# design.net
KiCad netlist of a schematic drawn in Altium Designer
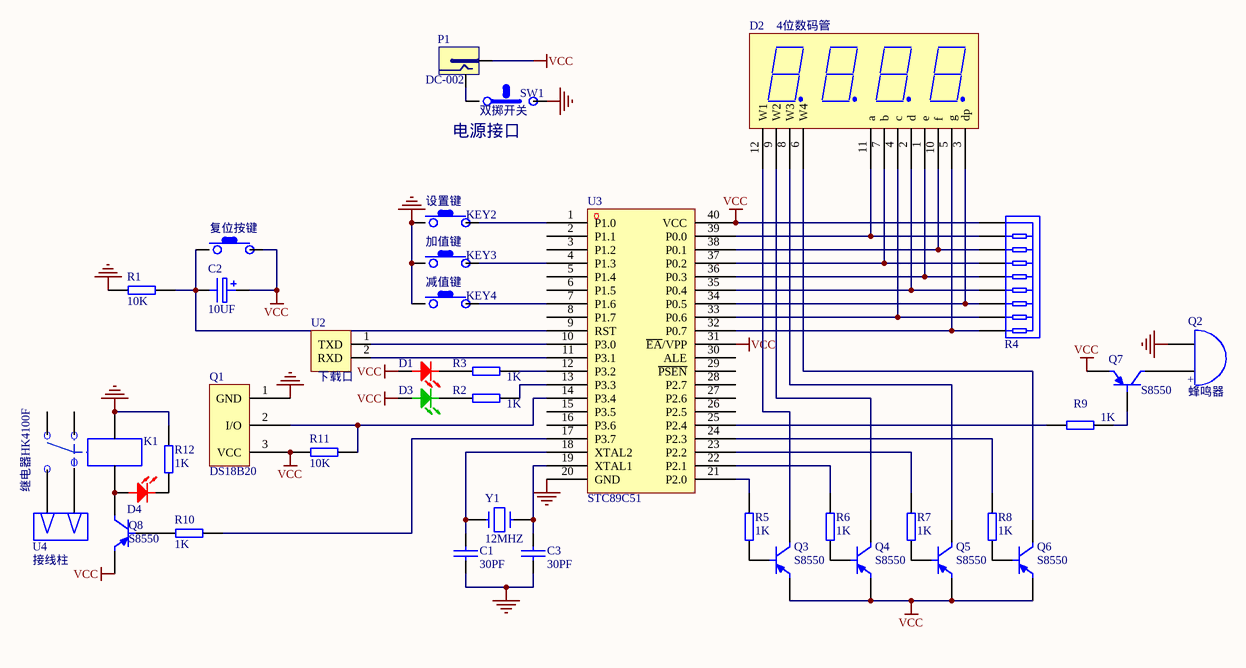
[diagram p0: 水温控制系统原理图.SchDoc]

(export (version "E")
  (design (tool "Eeschema 10.0.6"))
  (components
    (comp (ref "C1") (value "30PF") (footprint "R38") (libsource (lib "元件库") (part "瓷片电容")))
    (comp (ref "C2") (value "10UF") (footprint "CD4") (libsource (lib "元件库") (part "电解电容")))
    (comp (ref "C3") (value "30PF") (footprint "R38") (libsource (lib "元件库") (part "瓷片电容")))
    (comp (ref "D1") (value "LED-RED") (footprint "LED-RED") (libsource (lib "元件库") (part "LED-RED")))
    (comp (ref "D2") (value "4位数码管") (footprint "3641B") (libsource (lib "元件库") (part "4位数码管")))
    (comp (ref "D3") (value "LED-GREEN") (footprint "LED-GREEN") (libsource (lib "元件库") (part "LED-GREEN")))
    (comp (ref "D4") (value "LED-RED") (footprint "LED-RED") (libsource (lib "元件库") (part "LED-RED")))
    (comp (ref "K1") (value "继电器HK4100F") (footprint "HK4100F") (libsource (lib "元件库") (part "继电器HK4100F")))
    (comp (ref "KEY1") (value "复位按键") (footprint "SW") (libsource (lib "元件库") (part "微动开关")))
    (comp (ref "KEY2") (value "设置键") (footprint "SW") (libsource (lib "元件库") (part "微动开关")))
    (comp (ref "KEY3") (value "加值键") (footprint "SW") (libsource (lib "元件库") (part "微动开关")))
    (comp (ref "KEY4") (value "减值键") (footprint "SW") (libsource (lib "元件库") (part "微动开关")))
    (comp (ref "P1") (value "DC-002") (footprint "DC-002") (libsource (lib "元件库") (part "DC-002")))
    (comp (ref "Q1") (value "DS18B20") (footprint "XH3P") (libsource (lib "元件库") (part "DS18B20")))
    (comp (ref "Q2") (value "蜂鸣器") (footprint "蜂鸣器") (libsource (lib "元件库") (part "蜂鸣器")))
    (comp (ref "Q3") (value "S8550") (footprint "三极管") (libsource (lib "元件库") (part "S8550")))
    (comp (ref "Q4") (value "S8550") (footprint "三极管") (libsource (lib "元件库") (part "S8550")))
    (comp (ref "Q5") (value "S8550") (footprint "三极管") (libsource (lib "元件库") (part "S8550")))
    (comp (ref "Q6") (value "S8550") (footprint "三极管") (libsource (lib "元件库") (part "S8550")))
    (comp (ref "Q7") (value "S8550") (footprint "三极管") (libsource (lib "元件库") (part "S8550")))
    (comp (ref "Q8") (value "S8550") (footprint "三极管") (libsource (lib "元件库") (part "S8550")))
    (comp (ref "R1") (value "10K") (footprint "AXIAL-0.3") (libsource (lib "元件库") (part "RES")))
    (comp (ref "R2") (value "1K") (footprint "AXIAL-0.3") (libsource (lib "元件库") (part "RES")))
    (comp (ref "R3") (value "1K") (footprint "AXIAL-0.3") (libsource (lib "元件库") (part "RES")))
    (comp (ref "R4") (value "10k") (footprint "R*9") (libsource (lib "元件库") (part "排阻")))
    (comp (ref "R5") (value "1K") (footprint "AXIAL-0.3") (libsource (lib "元件库") (part "RES")))
    (comp (ref "R6") (value "1K") (footprint "AXIAL-0.3") (libsource (lib "元件库") (part "RES")))
    (comp (ref "R7") (value "1K") (footprint "AXIAL-0.3") (libsource (lib "元件库") (part "RES")))
    (comp (ref "R8") (value "1K") (footprint "AXIAL-0.3") (libsource (lib "元件库") (part "RES")))
    (comp (ref "R9") (value "1K") (footprint "AXIAL-0.3") (libsource (lib "元件库") (part "RES")))
    (comp (ref "R10") (value "1K") (footprint "AXIAL-0.3") (libsource (lib "元件库") (part "RES")))
    (comp (ref "R11") (value "10K") (footprint "AXIAL-0.3") (libsource (lib "元件库") (part "RES")))
    (comp (ref "R12") (value "1K") (footprint "AXIAL-0.3") (libsource (lib "元件库") (part "RES")))
    (comp (ref "SW1") (value "双掷开关") (footprint "SS12D07G5") (libsource (lib "元件库") (part "双掷开关")))
    (comp (ref "U2") (value "下载口") (footprint "HDR2") (libsource (lib "元件库") (part "下载口")))
    (comp (ref "U3") (value "STC89C51") (footprint "DIP40") (libsource (lib "元件库") (part "STC89C52")))
    (comp (ref "U4") (value "接线柱") (footprint "KF301-2P") (libsource (lib "元件库") (part "接线柱")))
    (comp (ref "Y1") (value "12MHZ") (footprint "XTAL") (libsource (lib "元件库") (part "XTAL")))
  )
  (nets
    (net (code "1") (name "GND") (class "Default")
      (node (ref "C1") (pin "2") (pinfunction "2_2") (pintype "passive"))
      (node (ref "C3") (pin "1") (pinfunction "1_1") (pintype "passive"))
      (node (ref "K1") (pin "5") (pinfunction "5_5") (pintype "passive"))
      (node (ref "KEY2") (pin "1") (pinfunction "3_1") (pintype "passive"))
      (node (ref "KEY3") (pin "1") (pinfunction "3_1") (pintype "passive"))
      (node (ref "KEY4") (pin "1") (pinfunction "3_1") (pintype "passive"))
      (node (ref "Q1") (pin "1") (pinfunction "GND_1") (pintype "passive"))
      (node (ref "Q2") (pin "2") (pinfunction "2_2") (pintype "passive"))
      (node (ref "R1") (pin "1") (pinfunction "1_1") (pintype "passive"))
      (node (ref "R12") (pin "1") (pinfunction "1_1") (pintype "passive"))
      (node (ref "SW1") (pin "2") (pinfunction "2_2") (pintype "passive"))
      (node (ref "U3") (pin "20") (pinfunction "GND_20") (pintype "passive"))
    )
    (net (code "2") (name "Net-(C2-E)") (class "Default")
      (node (ref "C2") (pin "2") (pinfunction "E_2") (pintype "passive"))
      (node (ref "KEY1") (pin "1") (pinfunction "3_1") (pintype "passive"))
      (node (ref "R1") (pin "2") (pinfunction "2_2") (pintype "passive"))
      (node (ref "U3") (pin "9") (pinfunction "RST_9") (pintype "passive"))
    )
    (net (code "3") (name "Net-(D1-Pad2)") (class "Default")
      (node (ref "D1") (pin "2") (pintype "passive"))
      (node (ref "R3") (pin "2") (pinfunction "2_2") (pintype "passive"))
    )
    (net (code "4") (name "Net-(D2-W1)") (class "Default")
      (node (ref "D2") (pin "12") (pinfunction "W1_12") (pintype "passive"))
      (node (ref "Q3") (pin "3") (pinfunction "C_3") (pintype "passive"))
    )
    (net (code "5") (name "Net-(D2-W2)") (class "Default")
      (node (ref "D2") (pin "9") (pinfunction "W2_9") (pintype "passive"))
      (node (ref "Q4") (pin "3") (pinfunction "C_3") (pintype "passive"))
    )
    (net (code "6") (name "Net-(D2-W3)") (class "Default")
      (node (ref "D2") (pin "8") (pinfunction "W3_8") (pintype "passive"))
      (node (ref "Q5") (pin "3") (pinfunction "C_3") (pintype "passive"))
    )
    (net (code "7") (name "Net-(D2-W4)") (class "Default")
      (node (ref "D2") (pin "6") (pinfunction "W4_6") (pintype "passive"))
      (node (ref "Q6") (pin "3") (pinfunction "C_3") (pintype "passive"))
    )
    (net (code "8") (name "Net-(D2-a)") (class "Default")
      (node (ref "D2") (pin "11") (pinfunction "a_11") (pintype "passive"))
      (node (ref "R4") (pin "2") (pinfunction "2_2") (pintype "passive"))
      (node (ref "U3") (pin "39") (pinfunction "P0.0_39") (pintype "passive"))
    )
    (net (code "9") (name "Net-(D2-b)") (class "Default")
      (node (ref "D2") (pin "7") (pinfunction "b_7") (pintype "passive"))
      (node (ref "R4") (pin "4") (pinfunction "4_4") (pintype "passive"))
      (node (ref "U3") (pin "37") (pinfunction "P0.2_37") (pintype "passive"))
    )
    (net (code "10") (name "Net-(D2-c)") (class "Default")
      (node (ref "D2") (pin "4") (pinfunction "c_4") (pintype "passive"))
      (node (ref "R4") (pin "8") (pinfunction "8_8") (pintype "passive"))
      (node (ref "U3") (pin "33") (pinfunction "P0.6_33") (pintype "passive"))
    )
    (net (code "11") (name "Net-(D2-d)") (class "Default")
      (node (ref "D2") (pin "2") (pinfunction "d_2") (pintype "passive"))
      (node (ref "R4") (pin "6") (pinfunction "6_6") (pintype "passive"))
      (node (ref "U3") (pin "35") (pinfunction "P0.4_35") (pintype "passive"))
    )
    (net (code "12") (name "Net-(D2-dp)") (class "Default")
      (node (ref "D2") (pin "3") (pinfunction "dp_3") (pintype "passive"))
      (node (ref "R4") (pin "7") (pinfunction "7_7") (pintype "passive"))
      (node (ref "U3") (pin "34") (pinfunction "P0.5_34") (pintype "passive"))
    )
    (net (code "13") (name "Net-(D2-e)") (class "Default")
      (node (ref "D2") (pin "1") (pinfunction "e_1") (pintype "passive"))
      (node (ref "R4") (pin "5") (pinfunction "5_5") (pintype "passive"))
      (node (ref "U3") (pin "36") (pinfunction "P0.3_36") (pintype "passive"))
    )
    (net (code "14") (name "Net-(D2-f)") (class "Default")
      (node (ref "D2") (pin "10") (pinfunction "f_10") (pintype "passive"))
      (node (ref "R4") (pin "3") (pinfunction "3_3") (pintype "passive"))
      (node (ref "U3") (pin "38") (pinfunction "P0.1_38") (pintype "passive"))
    )
    (net (code "15") (name "Net-(D2-g)") (class "Default")
      (node (ref "D2") (pin "5") (pinfunction "g_5") (pintype "passive"))
      (node (ref "R4") (pin "9") (pinfunction "9_9") (pintype "passive"))
      (node (ref "U3") (pin "32") (pinfunction "P0.7_32") (pintype "passive"))
    )
    (net (code "16") (name "Net-(D3-Pad2)") (class "Default")
      (node (ref "D3") (pin "2") (pintype "passive"))
      (node (ref "R2") (pin "2") (pinfunction "2_2") (pintype "passive"))
    )
    (net (code "17") (name "Net-(D4-Pad2)") (class "Default")
      (node (ref "D4") (pin "2") (pintype "passive"))
      (node (ref "R12") (pin "2") (pinfunction "2_2") (pintype "passive"))
    )
    (net (code "18") (name "Net-(K1-Pad1)") (class "Default")
      (node (ref "K1") (pin "1") (pinfunction "1_1") (pintype "passive"))
      (node (ref "U4") (pin "1") (pinfunction "1_1") (pintype "passive"))
    )
    (net (code "19") (name "Net-(K1-Pad4)") (class "Default")
      (node (ref "K1") (pin "4") (pinfunction "4_4") (pintype "passive"))
      (node (ref "U4") (pin "2") (pinfunction "2_2") (pintype "passive"))
    )
    (net (code "20") (name "Net-(KEY2-4)") (class "Default")
      (node (ref "KEY2") (pin "2") (pinfunction "4_2") (pintype "passive"))
      (node (ref "U3") (pin "1") (pinfunction "P1.0_1") (pintype "passive"))
    )
    (net (code "21") (name "Net-(KEY3-4)") (class "Default")
      (node (ref "KEY3") (pin "2") (pinfunction "4_2") (pintype "passive"))
      (node (ref "U3") (pin "4") (pinfunction "P1.3_4") (pintype "passive"))
    )
    (net (code "22") (name "Net-(KEY4-4)") (class "Default")
      (node (ref "KEY4") (pin "2") (pinfunction "4_2") (pintype "passive"))
      (node (ref "U3") (pin "7") (pinfunction "P1.6_7") (pintype "passive"))
    )
    (net (code "23") (name "Net-(P1-Pad2)") (class "Default")
      (node (ref "P1") (pin "2") (pinfunction "2_2") (pintype "passive"))
      (node (ref "SW1") (pin "1") (pinfunction "1_1") (pintype "passive"))
    )
    (net (code "24") (name "Net-(Q1-I{slash}O)") (class "Default")
      (node (ref "Q1") (pin "2") (pinfunction "I/O_2") (pintype "passive"))
      (node (ref "R11") (pin "1") (pinfunction "1_1") (pintype "passive"))
      (node (ref "U3") (pin "14") (pinfunction "P3.4_14") (pintype "passive"))
    )
    (net (code "25") (name "Net-(Q3-B)") (class "Default")
      (node (ref "Q3") (pin "2") (pinfunction "B_2") (pintype "passive"))
      (node (ref "R5") (pin "2") (pinfunction "2_2") (pintype "passive"))
    )
    (net (code "26") (name "Net-(Q4-B)") (class "Default")
      (node (ref "Q4") (pin "2") (pinfunction "B_2") (pintype "passive"))
      (node (ref "R6") (pin "2") (pinfunction "2_2") (pintype "passive"))
    )
    (net (code "27") (name "Net-(Q5-B)") (class "Default")
      (node (ref "Q5") (pin "2") (pinfunction "B_2") (pintype "passive"))
      (node (ref "R7") (pin "2") (pinfunction "2_2") (pintype "passive"))
    )
    (net (code "28") (name "Net-(Q6-B)") (class "Default")
      (node (ref "Q6") (pin "2") (pinfunction "B_2") (pintype "passive"))
      (node (ref "R8") (pin "2") (pinfunction "2_2") (pintype "passive"))
    )
    (net (code "29") (name "Net-(Q7-B)") (class "Default")
      (node (ref "Q7") (pin "2") (pinfunction "B_2") (pintype "passive"))
      (node (ref "R9") (pin "2") (pinfunction "2_2") (pintype "passive"))
    )
    (net (code "30") (name "Net-(Q7-C)") (class "Default")
      (node (ref "Q2") (pin "1") (pinfunction "1_1") (pintype "passive"))
      (node (ref "Q7") (pin "3") (pinfunction "C_3") (pintype "passive"))
    )
    (net (code "31") (name "Net-(Q8-B)") (class "Default")
      (node (ref "Q8") (pin "2") (pinfunction "B_2") (pintype "passive"))
      (node (ref "R10") (pin "1") (pinfunction "1_1") (pintype "passive"))
    )
    (net (code "32") (name "Net-(Q8-C)") (class "Default")
      (node (ref "D4") (pin "1") (pintype "passive"))
      (node (ref "K1") (pin "2") (pinfunction "2_2") (pintype "passive"))
      (node (ref "Q8") (pin "3") (pinfunction "C_3") (pintype "passive"))
    )
    (net (code "33") (name "Net-(U2-RXD)") (class "Default")
      (node (ref "U2") (pin "2") (pinfunction "RXD_2") (pintype "passive"))
      (node (ref "U3") (pin "11") (pinfunction "P3.1_11") (pintype "passive"))
    )
    (net (code "34") (name "Net-(U2-TXD)") (class "Default")
      (node (ref "U2") (pin "1") (pinfunction "TXD_1") (pintype "passive"))
      (node (ref "U3") (pin "10") (pinfunction "P3.0_10") (pintype "passive"))
    )
    (net (code "35") (name "Net-(U3-P2.0)") (class "Default")
      (node (ref "R5") (pin "1") (pinfunction "1_1") (pintype "passive"))
      (node (ref "U3") (pin "21") (pinfunction "P2.0_21") (pintype "passive"))
    )
    (net (code "36") (name "Net-(U3-P2.1)") (class "Default")
      (node (ref "R6") (pin "1") (pinfunction "1_1") (pintype "passive"))
      (node (ref "U3") (pin "22") (pinfunction "P2.1_22") (pintype "passive"))
    )
    (net (code "37") (name "Net-(U3-P2.2)") (class "Default")
      (node (ref "R7") (pin "1") (pinfunction "1_1") (pintype "passive"))
      (node (ref "U3") (pin "23") (pinfunction "P2.2_23") (pintype "passive"))
    )
    (net (code "38") (name "Net-(U3-P2.3)") (class "Default")
      (node (ref "R8") (pin "1") (pinfunction "1_1") (pintype "passive"))
      (node (ref "U3") (pin "24") (pinfunction "P2.3_24") (pintype "passive"))
    )
    (net (code "39") (name "Net-(U3-P2.4)") (class "Default")
      (node (ref "R9") (pin "1") (pinfunction "1_1") (pintype "passive"))
      (node (ref "U3") (pin "25") (pinfunction "P2.4_25") (pintype "passive"))
    )
    (net (code "40") (name "Net-(U3-P3.2)") (class "Default")
      (node (ref "R3") (pin "1") (pinfunction "1_1") (pintype "passive"))
      (node (ref "U3") (pin "12") (pinfunction "P3.2_12") (pintype "passive"))
    )
    (net (code "41") (name "Net-(U3-P3.3)") (class "Default")
      (node (ref "R2") (pin "1") (pinfunction "1_1") (pintype "passive"))
      (node (ref "U3") (pin "13") (pinfunction "P3.3_13") (pintype "passive"))
    )
    (net (code "42") (name "Net-(U3-P3.7)") (class "Default")
      (node (ref "R10") (pin "2") (pinfunction "2_2") (pintype "passive"))
      (node (ref "U3") (pin "17") (pinfunction "P3.7_17") (pintype "passive"))
    )
    (net (code "43") (name "Net-(U3-XTAL1)") (class "Default")
      (node (ref "C3") (pin "2") (pinfunction "2_2") (pintype "passive"))
      (node (ref "U3") (pin "19") (pinfunction "XTAL1_19") (pintype "passive"))
      (node (ref "Y1") (pin "1") (pinfunction "1_1") (pintype "passive"))
    )
    (net (code "44") (name "Net-(U3-XTAL2)") (class "Default")
      (node (ref "C1") (pin "1") (pinfunction "1_1") (pintype "passive"))
      (node (ref "U3") (pin "18") (pinfunction "XTAL2_18") (pintype "passive"))
      (node (ref "Y1") (pin "2") (pinfunction "2_2") (pintype "passive"))
    )
    (net (code "45") (name "VCC") (class "Default")
      (node (ref "C2") (pin "1") (pinfunction "1_1") (pintype "passive"))
      (node (ref "D1") (pin "1") (pintype "passive"))
      (node (ref "D3") (pin "1") (pintype "passive"))
      (node (ref "KEY1") (pin "2") (pinfunction "4_2") (pintype "passive"))
      (node (ref "P1") (pin "1") (pinfunction "1_1") (pintype "passive"))
      (node (ref "Q1") (pin "3") (pinfunction "VCC_3") (pintype "passive"))
      (node (ref "Q3") (pin "1") (pinfunction "E_1") (pintype "passive"))
      (node (ref "Q4") (pin "1") (pinfunction "E_1") (pintype "passive"))
      (node (ref "Q5") (pin "1") (pinfunction "E_1") (pintype "passive"))
      (node (ref "Q6") (pin "1") (pinfunction "E_1") (pintype "passive"))
      (node (ref "Q7") (pin "1") (pinfunction "E_1") (pintype "passive"))
      (node (ref "Q8") (pin "1") (pinfunction "E_1") (pintype "passive"))
      (node (ref "R11") (pin "2") (pinfunction "2_2") (pintype "passive"))
      (node (ref "R4") (pin "1") (pinfunction "1_1") (pintype "passive"))
      (node (ref "U3") (pin "31") (pinfunction "~{EA}/VPP_31") (pintype "passive"))
      (node (ref "U3") (pin "40") (pinfunction "VCC_40") (pintype "passive"))
    )
    (net (code "46") (name "unconnected-(K1-Pad3)") (class "Default")
      (node (ref "K1") (pin "3") (pinfunction "3_3") (pintype "passive"))
    )
    (net (code "47") (name "unconnected-(K1-Pad6)") (class "Default")
      (node (ref "K1") (pin "6") (pinfunction "6_6") (pintype "passive"))
    )
    (net (code "48") (name "unconnected-(U3-ALE-Pad30)") (class "Default")
      (node (ref "U3") (pin "30") (pinfunction "ALE_30") (pintype "passive"))
    )
    (net (code "49") (name "unconnected-(U3-P1.1-Pad2)") (class "Default")
      (node (ref "U3") (pin "2") (pinfunction "P1.1_2") (pintype "passive"))
    )
    (net (code "50") (name "unconnected-(U3-P1.2-Pad3)") (class "Default")
      (node (ref "U3") (pin "3") (pinfunction "P1.2_3") (pintype "passive"))
    )
    (net (code "51") (name "unconnected-(U3-P1.4-Pad5)") (class "Default")
      (node (ref "U3") (pin "5") (pinfunction "P1.4_5") (pintype "passive"))
    )
    (net (code "52") (name "unconnected-(U3-P1.5-Pad6)") (class "Default")
      (node (ref "U3") (pin "6") (pinfunction "P1.5_6") (pintype "passive"))
    )
    (net (code "53") (name "unconnected-(U3-P1.7-Pad8)") (class "Default")
      (node (ref "U3") (pin "8") (pinfunction "P1.7_8") (pintype "passive"))
    )
    (net (code "54") (name "unconnected-(U3-P2.5-Pad26)") (class "Default")
      (node (ref "U3") (pin "26") (pinfunction "P2.5_26") (pintype "passive"))
    )
    (net (code "55") (name "unconnected-(U3-P2.6-Pad27)") (class "Default")
      (node (ref "U3") (pin "27") (pinfunction "P2.6_27") (pintype "passive"))
    )
    (net (code "56") (name "unconnected-(U3-P2.7-Pad28)") (class "Default")
      (node (ref "U3") (pin "28") (pinfunction "P2.7_28") (pintype "passive"))
    )
    (net (code "57") (name "unconnected-(U3-P3.5-Pad15)") (class "Default")
      (node (ref "U3") (pin "15") (pinfunction "P3.5_15") (pintype "passive"))
    )
    (net (code "58") (name "unconnected-(U3-P3.6-Pad16)") (class "Default")
      (node (ref "U3") (pin "16") (pinfunction "P3.6_16") (pintype "passive"))
    )
    (net (code "59") (name "unconnected-(U3-~{PSEN}-Pad29)") (class "Default")
      (node (ref "U3") (pin "29") (pinfunction "~{PSEN}_29") (pintype "passive"))
    )
  )
)
